# qspi_flash.net
KiCad netlist of a schematic drawn in Altium Designer
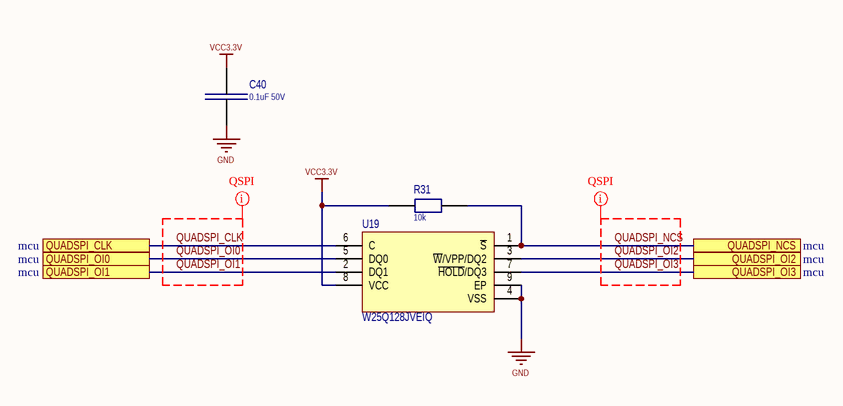
[diagram p0: qspi_flash.schdoc]

(export (version "E")
  (design (tool "Eeschema 10.0.6"))
  (components
    (comp (ref "C40")
      (value "0.1uF 50V")
      (footprint "C_0603")
      (description "Capacitor")
      (fields (field (name "PART") "CC0603KPX7R9BB104") (field (name "JLCPCB PART") "C14663"))
      (libsource (lib "AX_Altium_v2.3") (part "C0603"))
    )
    (comp (ref "R31")
      (value "10k")
      (footprint "R_0603")
      (description "Resistor")
      (fields (field (name "PART") "RC0603JR-0710KL") (field (name "JLCPCB PART") "C99198"))
      (libsource (lib "resistors") (part "RES_SMD"))
    )
    (comp (ref "U19")
      (value "W25Q128JVEIQ")
      (footprint "W-PDFN-8 (MLP8) – 8mm ? 6mm  Se")
      (description "Flash Memory")
      (fields (field (name "JLCPCB PART") "C2456297"))
      (libsource (lib "AX_Altium_v2.3") (part "MT25QL********W9-0SIT"))
    )
  )
  (nets
    (net (code "1") (name "/QUADSPI_CLK") (class "Default")
      (node (ref "U19") (pin "6") (pinfunction "C_6") (pintype "passive"))
    )
    (net (code "2") (name "/QUADSPI_NCS") (class "Default")
      (node (ref "R31") (pin "2") (pinfunction "2_2") (pintype "passive"))
      (node (ref "U19") (pin "1") (pinfunction "~{S}_1") (pintype "passive"))
    )
    (net (code "3") (name "/QUADSPI_OI0") (class "Default")
      (node (ref "U19") (pin "5") (pinfunction "DQ0_5") (pintype "passive"))
    )
    (net (code "4") (name "/QUADSPI_OI1") (class "Default")
      (node (ref "U19") (pin "2") (pinfunction "DQ1_2") (pintype "passive"))
    )
    (net (code "5") (name "/QUADSPI_OI2") (class "Default")
      (node (ref "U19") (pin "3") (pinfunction "~{W}/VPP/DQ2_3") (pintype "passive"))
    )
    (net (code "6") (name "/QUADSPI_OI3") (class "Default")
      (node (ref "U19") (pin "7") (pinfunction "~{HOLD}/DQ3_7") (pintype "passive"))
    )
    (net (code "7") (name "GND") (class "Default")
      (node (ref "C40") (pin "1") (pinfunction "1_1") (pintype "passive"))
      (node (ref "U19") (pin "4") (pinfunction "VSS_4") (pintype "passive"))
      (node (ref "U19") (pin "9") (pinfunction "EP_9") (pintype "passive"))
    )
    (net (code "8") (name "VCC3.3V") (class "Default")
      (node (ref "C40") (pin "2") (pinfunction "2_2") (pintype "passive"))
      (node (ref "R31") (pin "1") (pinfunction "1_1") (pintype "passive"))
      (node (ref "U19") (pin "8") (pinfunction "VCC_8") (pintype "passive"))
    )
  )
)
